# 05_-_POWER.net
KiCad netlist of a schematic drawn in Altium Designer
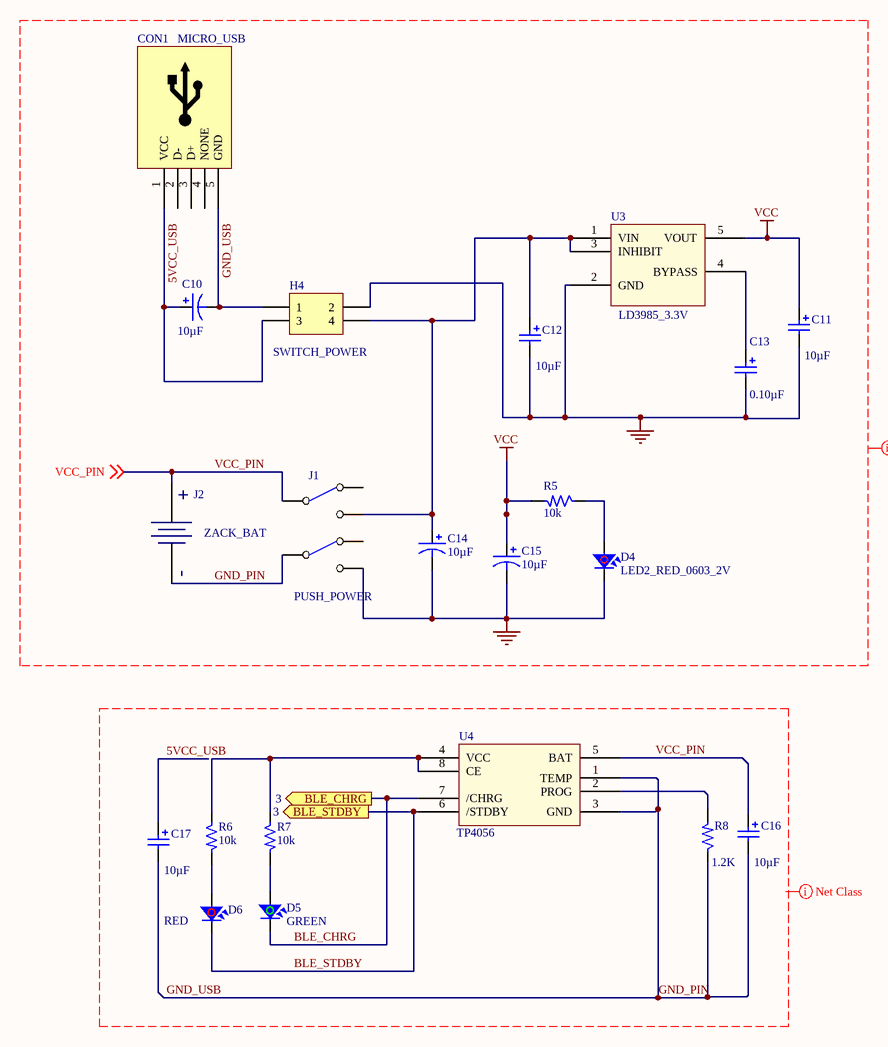
[diagram p0: [05] - POWER.SchDoc]

(export (version "E")
  (design (tool "Eeschema 10.0.6"))
  (components
    (comp (ref "C10")
      (value "C_106_0805_TANTALUM_16V")
      (footprint "CAP_SMD0805 - TANTALUM")
      (description "CAP TANT 10UF 16V 10% 0805")
      (fields
        (field (name "MANUFACTURER") "AVX Corporation")
        (field (name "MANUFACTURER PART NUMBER") "TPCR106K016R1800")
        (field (name "CAPACITANCE") "10µF")
      )
      (libsource (lib "ALTIUM_LIB") (part "C_106_0805_TANTALUM_16V"))
    )
    (comp (ref "C11")
      (value "C_106_0805_CERAMIC_16V")
      (footprint "CAP_SMD0805")
      (description "CAP CER 10UF 16V X5R 0805")
      (fields
        (field (name "MANUFACTURER") "Murata Electronics North America")
        (field (name "MANUFACTURER PART NUMBER") "GRM21BR61C106KE15K")
        (field (name "CAPACITANCE") "10µF")
      )
      (libsource (lib "ALTIUM_LIB") (part "C_106_0805_CERAMIC_16V"))
    )
    (comp (ref "C12")
      (value "C_106_0805_CERAMIC_16V")
      (footprint "CAP_SMD0805")
      (description "CAP CER 10UF 16V X5R 0805")
      (fields
        (field (name "MANUFACTURER") "Murata Electronics North America")
        (field (name "MANUFACTURER PART NUMBER") "GRM21BR61C106KE15K")
        (field (name "CAPACITANCE") "10µF")
      )
      (libsource (lib "ALTIUM_LIB") (part "C_106_0805_CERAMIC_16V"))
    )
    (comp (ref "C13")
      (value "C_104_0603_CERAMIC_16V")
      (footprint "CAP_SMD0603")
      (description "CAP CER 0.1UF 16V X7R 0603")
      (fields
        (field (name "MANUFACTURER") "Murata Electronics North America")
        (field (name "MANUFACTURER PART NUMBER") "GRM188R71C104KA01D")
        (field (name "CAPACITANCE") "0.10µF")
      )
      (libsource (lib "ALTIUM_LIB") (part "C_104_0603_CERAMIC_16V"))
    )
    (comp (ref "C14")
      (value "C_106_0805_TANTALUM_16V")
      (footprint "CAP_SMD0805 - TANTALUM")
      (description "CAP TANT 10UF 16V 10% 0805")
      (fields
        (field (name "MANUFACTURER") "AVX Corporation")
        (field (name "MANUFACTURER PART NUMBER") "TPCR106K016R1800")
        (field (name "CAPACITANCE") "10µF")
      )
      (libsource (lib "ALTIUM_LIB") (part "C_106_0805_TANTALUM_16V"))
    )
    (comp (ref "C15")
      (value "C_106_0805_TANTALUM_16V")
      (footprint "CAP_SMD0805 - TANTALUM")
      (description "CAP TANT 10UF 16V 10% 0805")
      (fields
        (field (name "MANUFACTURER") "AVX Corporation")
        (field (name "MANUFACTURER PART NUMBER") "TPCR106K016R1800")
        (field (name "CAPACITANCE") "10µF")
      )
      (libsource (lib "ALTIUM_LIB") (part "C_106_0805_TANTALUM_16V"))
    )
    (comp (ref "C16")
      (value "C_106_0805_CERAMIC_16V")
      (footprint "CAP_SMD0805")
      (description "CAP CER 10UF 16V X5R 0805")
      (fields
        (field (name "MANUFACTURER") "Murata Electronics North America")
        (field (name "MANUFACTURER PART NUMBER") "GRM21BR61C106KE15K")
        (field (name "CAPACITANCE") "10µF")
      )
      (libsource (lib "ALTIUM_LIB") (part "C_106_0805_CERAMIC_16V"))
    )
    (comp (ref "C17")
      (value "C_106_0805_CERAMIC_16V")
      (footprint "CAP_SMD0805")
      (description "CAP CER 10UF 16V X5R 0805")
      (fields
        (field (name "MANUFACTURER") "Murata Electronics North America")
        (field (name "MANUFACTURER PART NUMBER") "GRM21BR61C106KE15K")
        (field (name "CAPACITANCE") "10µF")
      )
      (libsource (lib "ALTIUM_LIB") (part "C_106_0805_CERAMIC_16V"))
    )
    (comp (ref "CON1")
      (value "MICRO_USB")
      (footprint "CON_MICRO_USB_HOLE")
      (description "CONN RCPT STD MICRO USB TYPE B")
      (fields
        (field (name "MANUFACTURER") "Amphenol FCI")
        (field (name "MANUFACTURER PART NUMBER") "10103593-0001LF")
      )
      (libsource (lib "ALTIUM_LIB") (part "CONNECT_MICRO_USB_SURFACE"))
    )
    (comp (ref "D4")
      (value "LED2_RED_0603_2V")
      (footprint "LED_RED_SMD0603")
      (description "LED RED CLEAR 0603 SMD")
      (fields
        (field (name "MANUFACTURER") "Lite-On Inc.")
        (field (name "MANUFACTURER PART NUMBER") "LTST-C191KRKT")
      )
      (libsource (lib "ALTIUM_LIB") (part "LED2_RED_0603_2V"))
    )
    (comp (ref "D5")
      (value "GREEN")
      (footprint "LED_GREEN_SMD0603")
      (description "LED GREEN CLEAR 0603 SMD")
      (fields
        (field (name "MANUFACTURER") "Lite-On Inc.")
        (field (name "MANUFACTURER PART NUMBER") "LTST-C191KGKT")
      )
      (libsource (lib "ALTIUM_LIB") (part "LED2_GREEN_0603_2V"))
    )
    (comp (ref "D6")
      (value "RED")
      (footprint "LED_RED_SMD0603")
      (description "LED RED CLEAR 0603 SMD")
      (fields
        (field (name "MANUFACTURER") "Lite-On Inc.")
        (field (name "MANUFACTURER PART NUMBER") "LTST-C191KRKT")
      )
      (libsource (lib "ALTIUM_LIB") (part "LED2_RED_0603_2V"))
    )
    (comp (ref "H4")
      (value "SWITCH_POWER")
      (footprint "HEADER2_MALE2_HOLE2.54")
      (description "CONN HEADER 4POS TIN SMD")
      (fields
        (field (name "MANUFACTURER") "Molex, LLC")
        (field (name "MANUFACTURER PART NUMBER") "0015912040")
      )
      (libsource (lib "ALTIUM_LIB") (part "HEADER2_MALE2_SURFACE_2.54_6.1MM"))
    )
    (comp (ref "J1")
      (value "PUSH_POWER")
      (footprint "SW6_DPDT_POWER")
      (description "SWITCH PUSH DPDT 0.1A 30V")
      (fields (field (name "MANUFACTURER") "Apem Inc.") (field (name "MANUFACTURER PART NUMBER") "MHPS2266"))
      (libsource (lib "ALTIUM_LIB") (part "SW6_DPDT_HOLE_PUSH_0.1A_30A"))
    )
    (comp (ref "J2")
      (value "ZACK_BAT")
      (footprint "ZACK_BAT")
      (description "CONN HEADER VERT 2POS .100 TIN")
      (fields
        (field (name "MANUFACTURER") "TE Connectivity AMP Connectors")
        (field (name "MANUFACTURER PART NUMBER") "640456-2")
      )
      (libsource (lib "ALTIUM_LIB") (part "ZACK2_HOLE_BATTERY_LOCK"))
    )
    (comp (ref "R5")
      (value "R_10K_SMD0603_1%_1/10W")
      (footprint "RES_SMD0603")
      (description "RES SMD 10K OHM 1% 1/10W 0603")
      (fields
        (field (name "MANUFACTURER") "Yageo")
        (field (name "MANUFACTURER PART NUMBER") "RC0603FR-0710KL")
        (field (name "RESISTANCE (OHMS)") "10k")
      )
      (libsource (lib "ALTIUM_LIB") (part "R_10K_SMD0603_1%_1/10W"))
    )
    (comp (ref "R6")
      (value "R_10K_SMD0603_1%_1/10W")
      (footprint "RES_SMD0603")
      (description "RES SMD 10K OHM 1% 1/10W 0603")
      (fields
        (field (name "MANUFACTURER") "Yageo")
        (field (name "MANUFACTURER PART NUMBER") "RC0603FR-0710KL")
        (field (name "RESISTANCE (OHMS)") "10k")
      )
      (libsource (lib "ALTIUM_LIB") (part "R_10K_SMD0603_1%_1/10W"))
    )
    (comp (ref "R7")
      (value "R_10K_SMD0603_1%_1/10W")
      (footprint "RES_SMD0603")
      (description "RES SMD 10K OHM 1% 1/10W 0603")
      (fields
        (field (name "MANUFACTURER") "Yageo")
        (field (name "MANUFACTURER PART NUMBER") "RC0603FR-0710KL")
        (field (name "RESISTANCE (OHMS)") "10k")
      )
      (libsource (lib "ALTIUM_LIB") (part "R_10K_SMD0603_1%_1/10W"))
    )
    (comp (ref "R8")
      (value "R_1K2_SMD0603_1%_1/10W")
      (footprint "RES_SMD0603")
      (description "RES SMD 1.2K OHM 1% 1/10W 0603")
      (fields
        (field (name "MANUFACTURER") "Yageo")
        (field (name "MANUFACTURER PART NUMBER") "RC0603FR-071K2L")
        (field (name "RESISTANCE (OHMS)") "1.2K")
      )
      (libsource (lib "ALTIUM_LIB") (part "R_1K2_SMD0603_1%_1/10W"))
    )
    (comp (ref "U3")
      (value "LD3985_3.3V")
      (footprint "POWER_LDO_LDR3985-3.3")
      (description "IC REG LDO 3.3V 0.15A SOT23-5")
      (fields
        (field (name "MANUFACTURER") "STMicroelectronics")
        (field (name "MANUFACTURER PART NUMBER") "LD3985M33R")
      )
      (libsource (lib "ALTIUM_LIB") (part "POWER_LDO_LD3985_3.3V_SOT-23-5"))
    )
    (comp (ref "U4")
      (value "TP4056")
      (footprint "POWER__CHARGE_TP4056")
      (description "IC CHARGR BATTERY L-ION  SOP8")
      (fields (field (name "MANUFACTURER") "NanJing"))
      (libsource (lib "ALTIUM_LIB") (part "POWER_CHARGE_TP4056_4.2V_SOP8"))
    )
  )
  (nets
    (net (code "1") (name "/5VCC_USB") (class "Default")
      (node (ref "C10") (pin "1") (pinfunction "1_1") (pintype "passive"))
      (node (ref "C17") (pin "1") (pinfunction "1_1") (pintype "passive"))
      (node (ref "CON1") (pin "1") (pinfunction "VCC_1") (pintype "passive"))
      (node (ref "H4") (pin "3") (pinfunction "3_3") (pintype "passive"))
    )
    (net (code "2") (name "/BLE_CHRG") (class "Default")
      (node (ref "D5") (pin "2") (pinfunction "2_2") (pintype "passive"))
      (node (ref "U4") (pin "7") (pinfunction "/CHRG_7") (pintype "passive"))
    )
    (net (code "3") (name "/BLE_STDBY") (class "Default")
      (node (ref "D6") (pin "2") (pinfunction "2_2") (pintype "passive"))
      (node (ref "U4") (pin "6") (pinfunction "/STDBY_6") (pintype "passive"))
    )
    (net (code "4") (name "/GND_PIN") (class "Default")
      (node (ref "C10") (pin "2") (pinfunction "2_2") (pintype "passive"))
      (node (ref "C16") (pin "2") (pinfunction "2_2") (pintype "passive"))
      (node (ref "C17") (pin "2") (pinfunction "2_2") (pintype "passive"))
      (node (ref "CON1") (pin "5") (pinfunction "GND_5") (pintype "passive"))
      (node (ref "H4") (pin "1") (pinfunction "1_1") (pintype "passive"))
      (node (ref "J1") (pin "5") (pinfunction "COMMON_5") (pintype "passive"))
      (node (ref "J2") (pin "2") (pinfunction "-_2") (pintype "passive"))
      (node (ref "R8") (pin "1") (pinfunction "1_1") (pintype "passive"))
      (node (ref "U4") (pin "1") (pinfunction "TEMP_1") (pintype "passive"))
      (node (ref "U4") (pin "3") (pinfunction "GND_3") (pintype "passive"))
    )
    (net (code "5") (name "GND") (class "Default")
      (node (ref "C11") (pin "2") (pinfunction "2_2") (pintype "passive"))
      (node (ref "C12") (pin "2") (pinfunction "2_2") (pintype "passive"))
      (node (ref "C13") (pin "2") (pinfunction "2_2") (pintype "passive"))
      (node (ref "C14") (pin "2") (pinfunction "2_2") (pintype "passive"))
      (node (ref "C15") (pin "2") (pinfunction "2_2") (pintype "passive"))
      (node (ref "D4") (pin "2") (pinfunction "2_2") (pintype "passive"))
      (node (ref "H4") (pin "2") (pinfunction "2_2") (pintype "passive"))
      (node (ref "J1") (pin "4") (pinfunction "NO_4") (pintype "passive"))
      (node (ref "U3") (pin "2") (pinfunction "GND_2") (pintype "passive"))
    )
    (net (code "6") (name "Net-(D4-Pad1)") (class "Default")
      (node (ref "D4") (pin "1") (pinfunction "1_1") (pintype "passive"))
      (node (ref "R5") (pin "1") (pinfunction "1_1") (pintype "passive"))
    )
    (net (code "7") (name "Net-(D5-Pad1)") (class "Default")
      (node (ref "D5") (pin "1") (pinfunction "1_1") (pintype "passive"))
      (node (ref "R7") (pin "2") (pinfunction "2_2") (pintype "passive"))
    )
    (net (code "8") (name "Net-(D6-Pad1)") (class "Default")
      (node (ref "D6") (pin "1") (pinfunction "1_1") (pintype "passive"))
      (node (ref "R6") (pin "2") (pinfunction "2_2") (pintype "passive"))
    )
    (net (code "9") (name "Net-(U3-BYPASS)") (class "Default")
      (node (ref "C13") (pin "1") (pinfunction "1_1") (pintype "passive"))
      (node (ref "U3") (pin "4") (pinfunction "BYPASS_4") (pintype "passive"))
    )
    (net (code "10") (name "Net-(U3-INHIBIT)") (class "Default")
      (node (ref "C12") (pin "1") (pinfunction "1_1") (pintype "passive"))
      (node (ref "C14") (pin "1") (pinfunction "1_1") (pintype "passive"))
      (node (ref "H4") (pin "4") (pinfunction "4_4") (pintype "passive"))
      (node (ref "J1") (pin "3") (pinfunction "NO_3") (pintype "passive"))
      (node (ref "U3") (pin "1") (pinfunction "VIN_1") (pintype "passive"))
      (node (ref "U3") (pin "3") (pinfunction "INHIBIT_3") (pintype "passive"))
    )
    (net (code "11") (name "Net-(U4-CE)") (class "Default")
      (node (ref "R6") (pin "1") (pinfunction "1_1") (pintype "passive"))
      (node (ref "R7") (pin "1") (pinfunction "1_1") (pintype "passive"))
      (node (ref "U4") (pin "4") (pinfunction "VCC_4") (pintype "passive"))
      (node (ref "U4") (pin "8") (pinfunction "CE_8") (pintype "passive"))
    )
    (net (code "12") (name "Net-(U4-PROG)") (class "Default")
      (node (ref "R8") (pin "2") (pinfunction "2_2") (pintype "passive"))
      (node (ref "U4") (pin "2") (pinfunction "PROG_2") (pintype "passive"))
    )
    (net (code "13") (name "VCC") (class "Default")
      (node (ref "C11") (pin "1") (pinfunction "1_1") (pintype "passive"))
      (node (ref "C15") (pin "1") (pinfunction "1_1") (pintype "passive"))
      (node (ref "R5") (pin "2") (pinfunction "2_2") (pintype "passive"))
      (node (ref "U3") (pin "5") (pinfunction "VOUT_5") (pintype "passive"))
    )
    (net (code "14") (name "VCC_PIN") (class "Default")
      (node (ref "C16") (pin "1") (pinfunction "1_1") (pintype "passive"))
      (node (ref "J1") (pin "2") (pinfunction "COMMON_2") (pintype "passive"))
      (node (ref "J2") (pin "1") (pinfunction "+_1") (pintype "passive"))
      (node (ref "U4") (pin "5") (pinfunction "BAT_5") (pintype "passive"))
    )
    (net (code "15") (name "unconnected-(CON1-D+-Pad3)") (class "Default")
      (node (ref "CON1") (pin "3") (pinfunction "D+_3") (pintype "passive"))
    )
    (net (code "16") (name "unconnected-(CON1-D--Pad2)") (class "Default")
      (node (ref "CON1") (pin "2") (pinfunction "D-_2") (pintype "passive"))
    )
    (net (code "17") (name "unconnected-(CON1-NONE-Pad4)") (class "Default")
      (node (ref "CON1") (pin "4") (pinfunction "NONE_4") (pintype "passive"))
    )
    (net (code "18") (name "unconnected-(J1-NC-Pad1)") (class "Default")
      (node (ref "J1") (pin "1") (pinfunction "NC_1") (pintype "passive"))
    )
    (net (code "19") (name "unconnected-(J1-NC-Pad6)") (class "Default")
      (node (ref "J1") (pin "6") (pinfunction "NC_6") (pintype "passive"))
    )
  )
)
